# BQ2980_EvalBoard.net
KiCad netlist of a schematic drawn in EAGLE
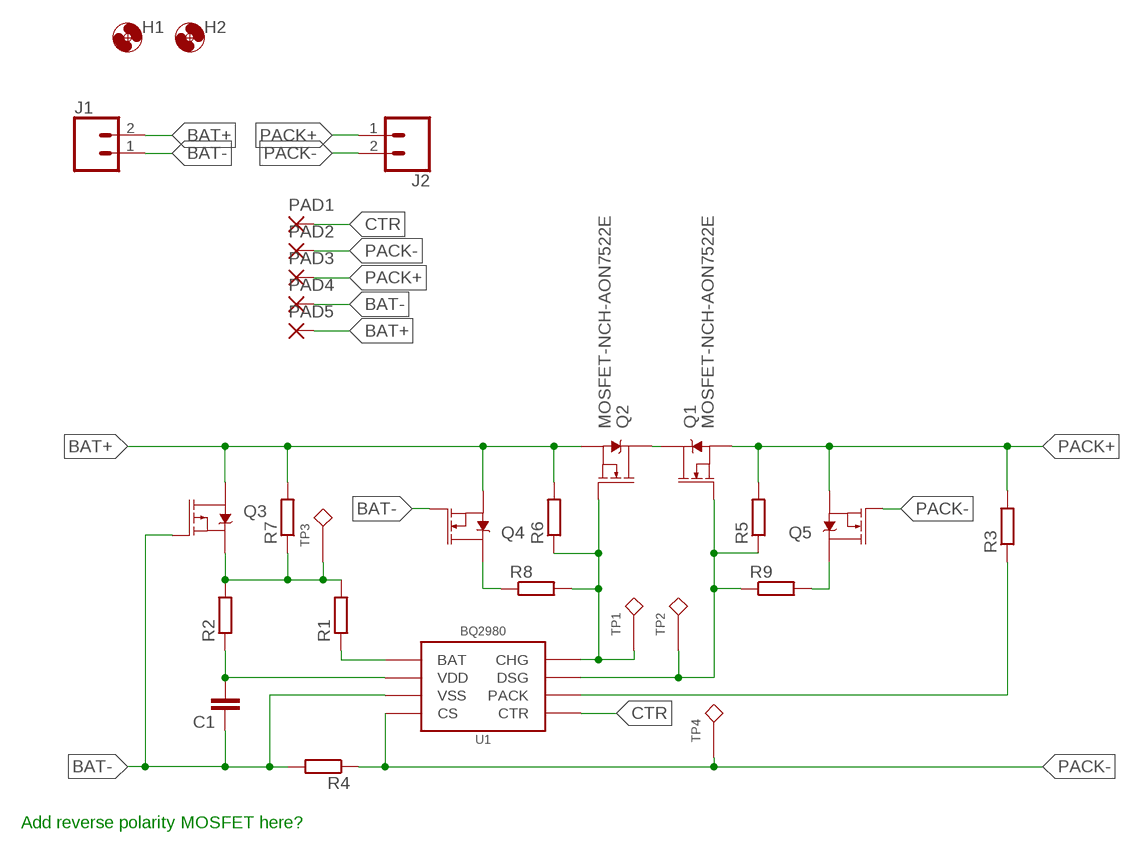
[diagram p0: schematic, sheet 1]

(export (version "E")
  (design (tool "Eeschema 10.0.6"))
  (components
    (comp (ref "C1")
      (value "C-EUC0603")
      (footprint "eagle-import:C0603")
      (libsource (lib "eagle-import") (part "C-EUC0603"))
    )
    (comp (ref "H1")
      (value "MOUNTING_HOLE2_NP")
      (footprint "eagle-import:2_56")
      (fields (field (name "MPN") "DNP"))
      (libsource (lib "eagle-import") (part "MOUNTING_HOLE2_NP"))
    )
    (comp (ref "H2")
      (value "MOUNTING_HOLE2_NP")
      (footprint "eagle-import:2_56")
      (fields (field (name "MPN") "DNP"))
      (libsource (lib "eagle-import") (part "MOUNTING_HOLE2_NP"))
    )
    (comp (ref "J1")
      (value "CONN_023.5MM_ROUND_RESTRICT")
      (footprint "eagle-import:SCREWTERMINAL-3.5MM-2_ROUND_RESTRICT")
      (fields (field (name "MF") "On Shore") (field (name "MPN") "OSTTE020161"))
      (libsource (lib "eagle-import") (part "CONN_023.5MM_ROUND_RESTRICT"))
    )
    (comp (ref "J2")
      (value "CONN_023.5MM_ROUND_RESTRICT")
      (footprint "eagle-import:SCREWTERMINAL-3.5MM-2_ROUND_RESTRICT")
      (fields (field (name "MF") "On Shore") (field (name "MPN") "OSTTE020161"))
      (libsource (lib "eagle-import") (part "CONN_023.5MM_ROUND_RESTRICT"))
    )
    (comp (ref "PAD1")
      (value "SMD1,27")
      (footprint "eagle-import:SMD1,27-2,54")
      (fields (field (name "MPN") "DNP"))
      (libsource (lib "eagle-import") (part "SMD1,27"))
    )
    (comp (ref "PAD2")
      (value "SMD1,27")
      (footprint "eagle-import:SMD1,27-2,54")
      (fields (field (name "MPN") "DNP"))
      (libsource (lib "eagle-import") (part "SMD1,27"))
    )
    (comp (ref "PAD3")
      (value "SMD1,27")
      (footprint "eagle-import:SMD1,27-2,54")
      (fields (field (name "MPN") "DNP"))
      (libsource (lib "eagle-import") (part "SMD1,27"))
    )
    (comp (ref "PAD4")
      (value "SMD1,27")
      (footprint "eagle-import:SMD1,27-2,54")
      (fields (field (name "MPN") "DNP"))
      (libsource (lib "eagle-import") (part "SMD1,27"))
    )
    (comp (ref "PAD5")
      (value "SMD1,27")
      (footprint "eagle-import:SMD1,27-2,54")
      (fields (field (name "MPN") "DNP"))
      (libsource (lib "eagle-import") (part "SMD1,27"))
    )
    (comp (ref "Q1")
      (value "MOSFET-NCH-AON7522E")
      (footprint "eagle-import:DFN3X3A_8L_EP1_P")
      (fields (field (name "MF") "Alpha & Omega") (field (name "MPN") "AON7522E"))
      (libsource (lib "eagle-import") (part "MOSFET-NCH-AON7522E"))
    )
    (comp (ref "Q2")
      (value "MOSFET-NCH-AON7522E")
      (footprint "eagle-import:DFN3X3A_8L_EP1_P")
      (fields (field (name "MF") "Alpha & Omega") (field (name "MPN") "AON7522E"))
      (libsource (lib "eagle-import") (part "MOSFET-NCH-AON7522E"))
    )
    (comp (ref "Q3")
      (value "MOSFET_PCH-NX2301P")
      (footprint "eagle-import:SOT23-3")
      (fields (field (name "MF") "Nexperia") (field (name "MPN") "NX2301P,215"))
      (libsource (lib "eagle-import") (part "MOSFET_PCH-NX2301P"))
    )
    (comp (ref "Q4")
      (value "2N7002")
      (footprint "eagle-import:SOT323")
      (fields (field (name "MF") "Diodes Incorporated") (field (name "MPN") "2N7002W-7-F"))
      (libsource (lib "eagle-import") (part "MOSFET-NCH-2N7002PW"))
    )
    (comp (ref "Q5")
      (value "2N7002")
      (footprint "eagle-import:SOT323")
      (fields (field (name "MF") "Diodes Incorporated") (field (name "MPN") "2N7002W-7-F"))
      (libsource (lib "eagle-import") (part "MOSFET-NCH-2N7002PW"))
    )
    (comp (ref "R1")
      (value "R-EU_R0603")
      (footprint "eagle-import:R0603")
      (fields (field (name "MF") "Yageo"))
      (libsource (lib "eagle-import") (part "R-EU_R0603"))
    )
    (comp (ref "R2")
      (value "R-EU_R0603")
      (footprint "eagle-import:R0603")
      (fields (field (name "MF") "Yageo"))
      (libsource (lib "eagle-import") (part "R-EU_R0603"))
    )
    (comp (ref "R3")
      (value "R-EU_R0603")
      (footprint "eagle-import:R0603")
      (fields (field (name "MF") "Yageo"))
      (libsource (lib "eagle-import") (part "R-EU_R0603"))
    )
    (comp (ref "R4")
      (value "R-EU_R0805")
      (footprint "eagle-import:R0805")
      (libsource (lib "eagle-import") (part "R-EU_R0805"))
    )
    (comp (ref "R5")
      (value "R-EU_R0603")
      (footprint "eagle-import:R0603")
      (fields (field (name "MF") "Yageo"))
      (libsource (lib "eagle-import") (part "R-EU_R0603"))
    )
    (comp (ref "R6")
      (value "R-EU_R0603")
      (footprint "eagle-import:R0603")
      (fields (field (name "MF") "Yageo"))
      (libsource (lib "eagle-import") (part "R-EU_R0603"))
    )
    (comp (ref "R7")
      (value "R-EU_R0603")
      (footprint "eagle-import:R0603")
      (fields (field (name "MF") "Yageo"))
      (libsource (lib "eagle-import") (part "R-EU_R0603"))
    )
    (comp (ref "R8")
      (value "R-EU_R0603")
      (footprint "eagle-import:R0603")
      (fields (field (name "MF") "Yageo"))
      (libsource (lib "eagle-import") (part "R-EU_R0603"))
    )
    (comp (ref "R9")
      (value "R-EU_R0603")
      (footprint "eagle-import:R0603")
      (fields (field (name "MF") "Yageo"))
      (libsource (lib "eagle-import") (part "R-EU_R0603"))
    )
    (comp (ref "TP1")
      (value "TESTPOINTRCU")
      (footprint "eagle-import:TESTPOINT_0603")
      (fields (field (name "MF") "TE Connectivity") (field (name "MPN") "RCU-0C"))
      (libsource (lib "eagle-import") (part "TESTPOINTRCU"))
    )
    (comp (ref "TP2")
      (value "TESTPOINTRCU")
      (footprint "eagle-import:TESTPOINT_0603")
      (fields (field (name "MF") "TE Connectivity") (field (name "MPN") "RCU-0C"))
      (libsource (lib "eagle-import") (part "TESTPOINTRCU"))
    )
    (comp (ref "TP3")
      (value "TESTPOINTRCU")
      (footprint "eagle-import:TESTPOINT_0603")
      (fields (field (name "MF") "TE Connectivity") (field (name "MPN") "RCU-0C"))
      (libsource (lib "eagle-import") (part "TESTPOINTRCU"))
    )
    (comp (ref "TP4")
      (value "TESTPOINTRCU")
      (footprint "eagle-import:TESTPOINT_0603")
      (fields (field (name "MF") "TE Connectivity") (field (name "MPN") "RCU-0C"))
      (libsource (lib "eagle-import") (part "TESTPOINTRCU"))
    )
    (comp (ref "U1")
      (value "BQ2980RUG")
      (footprint "eagle-import:RUG_S-PQFP-N8")
      (fields (field (name "MF") "TI") (field (name "MPN") "BQ298000RUGT"))
      (libsource (lib "eagle-import") (part "BQ2980RUG"))
    )
  )
  (nets
    (net (code "1") (name "BAT+") (class "Default")
      (node (ref "J1") (pin "2") (pinfunction "2_2") (pintype "passive"))
      (node (ref "PAD5") (pin "1") (pinfunction "P_1") (pintype "passive"))
      (node (ref "Q2") (pin "S@1") (pinfunction "S_S@1") (pintype "bidirectional"))
      (node (ref "Q2") (pin "S@2") (pinfunction "S_S@2") (pintype "bidirectional"))
      (node (ref "Q2") (pin "S@3") (pinfunction "S_S@3") (pintype "bidirectional"))
      (node (ref "Q3") (pin "3") (pinfunction "D_3") (pintype "bidirectional"))
      (node (ref "Q4") (pin "2") (pinfunction "S_2") (pintype "bidirectional"))
      (node (ref "R6") (pin "2") (pinfunction "2_2") (pintype "passive"))
      (node (ref "R7") (pin "2") (pinfunction "2_2") (pintype "passive"))
    )
    (net (code "2") (name "BAT-") (class "Default")
      (node (ref "C1") (pin "1") (pinfunction "1_1") (pintype "passive"))
      (node (ref "J1") (pin "1") (pinfunction "1_1") (pintype "passive"))
      (node (ref "PAD4") (pin "1") (pinfunction "P_1") (pintype "passive"))
      (node (ref "Q3") (pin "1") (pinfunction "G_1") (pintype "bidirectional"))
      (node (ref "Q4") (pin "1") (pinfunction "G_1") (pintype "bidirectional"))
      (node (ref "R4") (pin "2") (pinfunction "2_2") (pintype "passive"))
      (node (ref "U1") (pin "3") (pinfunction "VSS_3") (pintype "power_in"))
    )
    (net (code "3") (name "CTR") (class "Default")
      (node (ref "PAD1") (pin "1") (pinfunction "P_1") (pintype "passive"))
      (node (ref "U1") (pin "5") (pinfunction "CTR_5") (pintype "input"))
    )
    (net (code "4") (name "Net-(Q1-PadD)") (class "Default")
      (node (ref "Q1") (pin "D") (pinfunction "D_D") (pintype "bidirectional"))
      (node (ref "Q2") (pin "D") (pinfunction "D_D") (pintype "bidirectional"))
    )
    (net (code "5") (name "Net-(Q3-S)") (class "Default")
      (node (ref "Q3") (pin "2") (pinfunction "S_2") (pintype "bidirectional"))
      (node (ref "R1") (pin "2") (pinfunction "2_2") (pintype "passive"))
      (node (ref "R2") (pin "2") (pinfunction "2_2") (pintype "passive"))
      (node (ref "R7") (pin "1") (pinfunction "1_1") (pintype "passive"))
      (node (ref "TP3") (pin "1") (pinfunction "P$1_1") (pintype "bidirectional"))
    )
    (net (code "6") (name "Net-(Q4-D)") (class "Default")
      (node (ref "Q4") (pin "3") (pinfunction "D_3") (pintype "bidirectional"))
      (node (ref "R8") (pin "1") (pinfunction "1_1") (pintype "passive"))
    )
    (net (code "7") (name "Net-(Q5-D)") (class "Default")
      (node (ref "Q5") (pin "3") (pinfunction "D_3") (pintype "bidirectional"))
      (node (ref "R9") (pin "2") (pinfunction "2_2") (pintype "passive"))
    )
    (net (code "8") (name "Net-(TP1-P$1)") (class "Default")
      (node (ref "Q2") (pin "G") (pinfunction "G_G") (pintype "bidirectional"))
      (node (ref "R6") (pin "1") (pinfunction "1_1") (pintype "passive"))
      (node (ref "R8") (pin "2") (pinfunction "2_2") (pintype "passive"))
      (node (ref "TP1") (pin "1") (pinfunction "P$1_1") (pintype "bidirectional"))
      (node (ref "U1") (pin "8") (pinfunction "CHG_8") (pintype "output"))
    )
    (net (code "9") (name "Net-(TP2-P$1)") (class "Default")
      (node (ref "Q1") (pin "G") (pinfunction "G_G") (pintype "bidirectional"))
      (node (ref "R5") (pin "1") (pinfunction "1_1") (pintype "passive"))
      (node (ref "R9") (pin "1") (pinfunction "1_1") (pintype "passive"))
      (node (ref "TP2") (pin "1") (pinfunction "P$1_1") (pintype "bidirectional"))
      (node (ref "U1") (pin "7") (pinfunction "DSG_7") (pintype "output"))
    )
    (net (code "10") (name "Net-(U1-BAT)") (class "Default")
      (node (ref "R1") (pin "1") (pinfunction "1_1") (pintype "passive"))
      (node (ref "U1") (pin "1") (pinfunction "BAT_1") (pintype "power_in"))
    )
    (net (code "11") (name "Net-(U1-PACK)") (class "Default")
      (node (ref "R3") (pin "1") (pinfunction "1_1") (pintype "passive"))
      (node (ref "U1") (pin "6") (pinfunction "PACK_6") (pintype "input"))
    )
    (net (code "12") (name "Net-(U1-VDD)") (class "Default")
      (node (ref "C1") (pin "2") (pinfunction "2_2") (pintype "passive"))
      (node (ref "R2") (pin "1") (pinfunction "1_1") (pintype "passive"))
      (node (ref "U1") (pin "2") (pinfunction "VDD_2") (pintype "power_in"))
    )
    (net (code "13") (name "PACK+") (class "Default")
      (node (ref "J2") (pin "1") (pinfunction "1_1") (pintype "passive"))
      (node (ref "PAD3") (pin "1") (pinfunction "P_1") (pintype "passive"))
      (node (ref "Q1") (pin "S@1") (pinfunction "S_S@1") (pintype "bidirectional"))
      (node (ref "Q1") (pin "S@2") (pinfunction "S_S@2") (pintype "bidirectional"))
      (node (ref "Q1") (pin "S@3") (pinfunction "S_S@3") (pintype "bidirectional"))
      (node (ref "Q5") (pin "2") (pinfunction "S_2") (pintype "bidirectional"))
      (node (ref "R3") (pin "2") (pinfunction "2_2") (pintype "passive"))
      (node (ref "R5") (pin "2") (pinfunction "2_2") (pintype "passive"))
    )
    (net (code "14") (name "PACK-") (class "Default")
      (node (ref "J2") (pin "2") (pinfunction "2_2") (pintype "passive"))
      (node (ref "PAD2") (pin "1") (pinfunction "P_1") (pintype "passive"))
      (node (ref "Q5") (pin "1") (pinfunction "G_1") (pintype "bidirectional"))
      (node (ref "R4") (pin "1") (pinfunction "1_1") (pintype "passive"))
      (node (ref "TP4") (pin "1") (pinfunction "P$1_1") (pintype "bidirectional"))
      (node (ref "U1") (pin "4") (pinfunction "CS_4") (pintype "input"))
    )
  )
)
